# Sheet1.net
KiCad netlist of a schematic drawn in Altium Designer
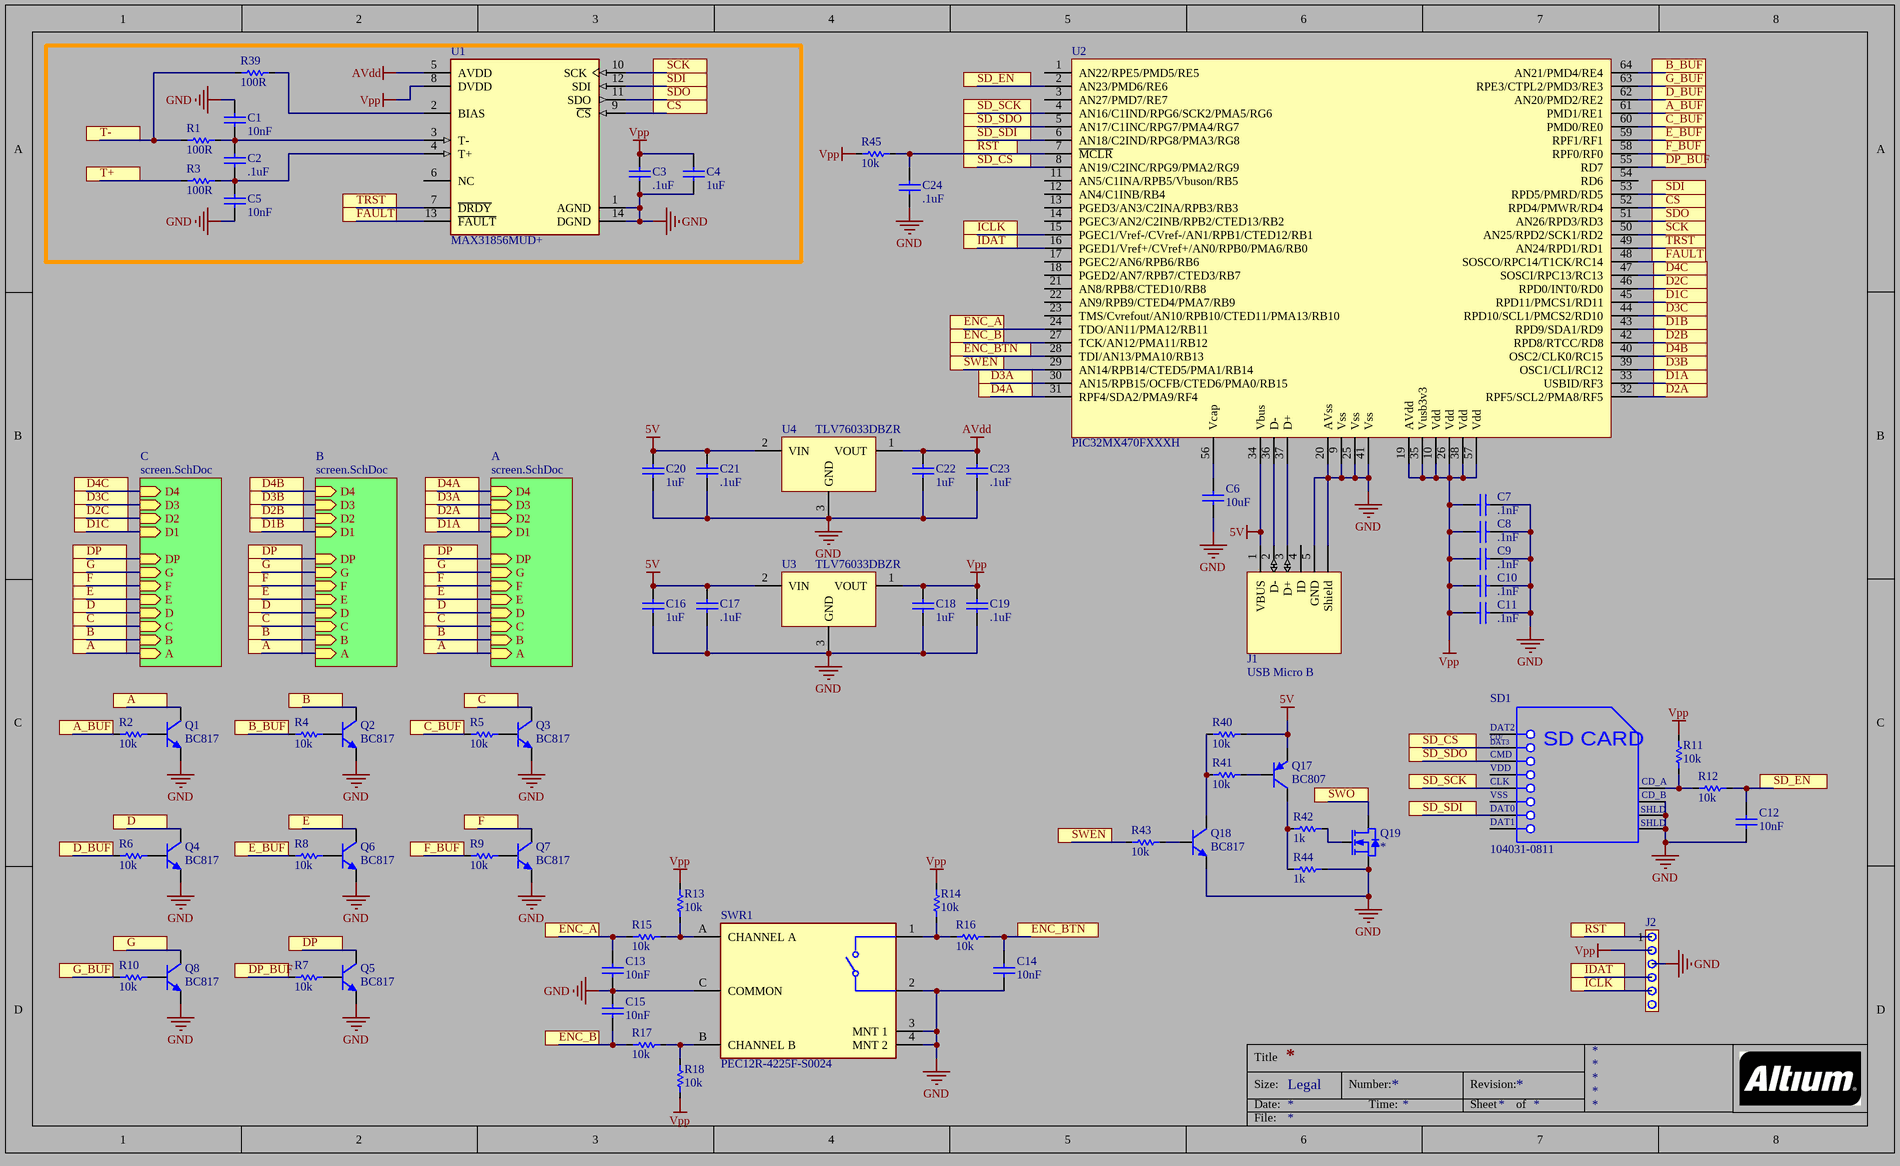
[diagram p0: Sheet1.SchDoc]

(export (version "E")
  (design (tool "Eeschema 10.0.6"))
  (components
    (comp (ref "C1")
      (value "10nF")
      (footprint "Size_0603_N")
      (description "=Value")
      (fields (field (name "Comment") "10nF, *, *, *, Size_0603_N"))
      (libsource (lib "A_Passive") (part "-Cap Non-Pol"))
    )
    (comp (ref "C2")
      (value ".1uF")
      (footprint "Size_0603_N")
      (description "=Value")
      (fields (field (name "Comment") ".1uF, *, *, *, Size_0603_N"))
      (libsource (lib "A_Passive") (part "-Cap Non-Pol"))
    )
    (comp (ref "C3")
      (value ".1uF")
      (footprint "Size_0603_N")
      (description "=Value")
      (fields (field (name "Comment") ".1uF, *, *, *, Size_0603_N"))
      (libsource (lib "A_Passive") (part "-Cap Non-Pol"))
    )
    (comp (ref "C4")
      (value "1uF")
      (footprint "Size_0805_N")
      (description "=Value")
      (fields (field (name "Comment") "1uF, *, *, *, Size_0805_N"))
      (libsource (lib "A_Passive") (part "-Cap Non-Pol"))
    )
    (comp (ref "C5")
      (value "10nF")
      (footprint "Size_0603_N")
      (description "=Value")
      (fields (field (name "Comment") "10nF, *, *, *, Size_0603_N"))
      (libsource (lib "A_Passive") (part "-Cap Non-Pol"))
    )
    (comp (ref "C6")
      (value "10uF")
      (footprint "Size_0805_N")
      (description "=Value")
      (fields (field (name "Comment") "10uF, *, *, *, Size_0805_N"))
      (libsource (lib "A_Passive") (part "-Cap Non-Pol"))
    )
    (comp (ref "C7")
      (value ".1nF")
      (footprint "Size_0603_N")
      (description "=Value")
      (fields (field (name "Comment") ".1nF, *, *, *, Size_0603_N"))
      (libsource (lib "A_Passive") (part "-Cap Non-Pol"))
    )
    (comp (ref "C8")
      (value ".1nF")
      (footprint "Size_0603_N")
      (description "=Value")
      (fields (field (name "Comment") ".1nF, *, *, *, Size_0603_N"))
      (libsource (lib "A_Passive") (part "-Cap Non-Pol"))
    )
    (comp (ref "C9")
      (value ".1nF")
      (footprint "Size_0603_N")
      (description "=Value")
      (fields (field (name "Comment") ".1nF, *, *, *, Size_0603_N"))
      (libsource (lib "A_Passive") (part "-Cap Non-Pol"))
    )
    (comp (ref "C10")
      (value ".1nF")
      (footprint "Size_0603_N")
      (description "=Value")
      (fields (field (name "Comment") ".1nF, *, *, *, Size_0603_N"))
      (libsource (lib "A_Passive") (part "-Cap Non-Pol"))
    )
    (comp (ref "C11")
      (value ".1nF")
      (footprint "Size_0603_N")
      (description "=Value")
      (fields (field (name "Comment") ".1nF, *, *, *, Size_0603_N"))
      (libsource (lib "A_Passive") (part "-Cap Non-Pol"))
    )
    (comp (ref "C12")
      (value "10nF")
      (footprint "Size_0603_N")
      (description "=Value")
      (fields (field (name "Comment") "10nF, *, *, *, Size_0603_N"))
      (libsource (lib "A_Passive") (part "-Cap Non-Pol"))
    )
    (comp (ref "C13")
      (value "10nF")
      (footprint "Size_0603_N")
      (description "=Value")
      (fields (field (name "Comment") "10nF, *, *, *, Size_0603_N"))
      (libsource (lib "A_Passive") (part "-Cap Non-Pol"))
    )
    (comp (ref "C14")
      (value "10nF")
      (footprint "Size_0603_N")
      (description "=Value")
      (fields (field (name "Comment") "10nF, *, *, *, Size_0603_N"))
      (libsource (lib "A_Passive") (part "-Cap Non-Pol"))
    )
    (comp (ref "C15")
      (value "10nF")
      (footprint "Size_0603_N")
      (description "=Value")
      (fields (field (name "Comment") "10nF, *, *, *, Size_0603_N"))
      (libsource (lib "A_Passive") (part "-Cap Non-Pol"))
    )
    (comp (ref "C16")
      (value "1uF")
      (footprint "Size_0805_N")
      (description "=Value")
      (fields (field (name "Comment") "1uF, *, *, *, Size_0805_N"))
      (libsource (lib "A_Passive") (part "-Cap Non-Pol"))
    )
    (comp (ref "C17")
      (value ".1uF")
      (footprint "Size_0603_N")
      (description "=Value")
      (fields (field (name "Comment") ".1uF, *, *, *, Size_0603_N"))
      (libsource (lib "A_Passive") (part "-Cap Non-Pol"))
    )
    (comp (ref "C18")
      (value "1uF")
      (footprint "Size_0805_N")
      (description "=Value")
      (fields (field (name "Comment") "1uF, *, *, *, Size_0805_N"))
      (libsource (lib "A_Passive") (part "-Cap Non-Pol"))
    )
    (comp (ref "C19")
      (value ".1uF")
      (footprint "Size_0603_N")
      (description "=Value")
      (fields (field (name "Comment") ".1uF, *, *, *, Size_0603_N"))
      (libsource (lib "A_Passive") (part "-Cap Non-Pol"))
    )
    (comp (ref "C20")
      (value "1uF")
      (footprint "Size_0805_N")
      (description "=Value")
      (fields (field (name "Comment") "1uF, *, *, *, Size_0805_N"))
      (libsource (lib "A_Passive") (part "-Cap Non-Pol"))
    )
    (comp (ref "C21")
      (value ".1uF")
      (footprint "Size_0603_N")
      (description "=Value")
      (fields (field (name "Comment") ".1uF, *, *, *, Size_0603_N"))
      (libsource (lib "A_Passive") (part "-Cap Non-Pol"))
    )
    (comp (ref "C22")
      (value "1uF")
      (footprint "Size_0805_N")
      (description "=Value")
      (fields (field (name "Comment") "1uF, *, *, *, Size_0805_N"))
      (libsource (lib "A_Passive") (part "-Cap Non-Pol"))
    )
    (comp (ref "C23")
      (value ".1uF")
      (footprint "Size_0603_N")
      (description "=Value")
      (fields (field (name "Comment") ".1uF, *, *, *, Size_0603_N"))
      (libsource (lib "A_Passive") (part "-Cap Non-Pol"))
    )
    (comp (ref "C24")
      (value ".1uF")
      (footprint "Size_0603_N")
      (description "=Value")
      (fields (field (name "Comment") ".1uF, *, *, *, Size_0603_N"))
      (libsource (lib "A_Passive") (part "-Cap Non-Pol"))
    )
    (comp (ref "J1")
      (value "USB Micro B")
      (footprint "USB-MICRO-B (10118194-0001LF)")
      (description "Female Micro USB Type B")
      (libsource (lib "A_Connector") (part "USB Micro B"))
    )
    (comp (ref "J2")
      (value "~")
      (footprint "HDR1X6 VERT - L")
      (libsource (lib "A_Connector") (part "Header 1-6"))
    )
    (comp (ref "Q1")
      (value "BC817")
      (footprint "SOT23-3")
      (description "NPN General Purpose")
      (libsource (lib "A_Semi") (part "1-BJT_NPN"))
    )
    (comp (ref "Q2")
      (value "BC817")
      (footprint "SOT23-3")
      (description "NPN General Purpose")
      (libsource (lib "A_Semi") (part "1-BJT_NPN"))
    )
    (comp (ref "Q3")
      (value "BC817")
      (footprint "SOT23-3")
      (description "NPN General Purpose")
      (libsource (lib "A_Semi") (part "1-BJT_NPN"))
    )
    (comp (ref "Q4")
      (value "BC817")
      (footprint "SOT23-3")
      (description "NPN General Purpose")
      (libsource (lib "A_Semi") (part "1-BJT_NPN"))
    )
    (comp (ref "Q5")
      (value "BC817")
      (footprint "SOT23-3")
      (description "NPN General Purpose")
      (libsource (lib "A_Semi") (part "1-BJT_NPN"))
    )
    (comp (ref "Q6")
      (value "BC817")
      (footprint "SOT23-3")
      (description "NPN General Purpose")
      (libsource (lib "A_Semi") (part "1-BJT_NPN"))
    )
    (comp (ref "Q7")
      (value "BC817")
      (footprint "SOT23-3")
      (description "NPN General Purpose")
      (libsource (lib "A_Semi") (part "1-BJT_NPN"))
    )
    (comp (ref "Q8")
      (value "BC817")
      (footprint "SOT23-3")
      (description "NPN General Purpose")
      (libsource (lib "A_Semi") (part "1-BJT_NPN"))
    )
    (comp (ref "Q17") (value "BC807") (footprint "SOT23-3") (libsource (lib "A_Semi") (part "1-BJT-PNP")))
    (comp (ref "Q18")
      (value "BC817")
      (footprint "SOT23-3")
      (description "NPN General Purpose")
      (libsource (lib "A_Semi") (part "1-BJT_NPN"))
    )
    (comp (ref "Q19")
      (value "*")
      (footprint "SOT23-3")
      (description "N-Channel Mosfet")
      (libsource (lib "A_Semi") (part "1-Mosfet_N"))
    )
    (comp (ref "R1")
      (value "100R")
      (footprint "Size_0603_N")
      (description "=Value")
      (fields (field (name "TOLERANCE") "1%") (field (name "Comment") "100R, *"))
      (libsource (lib "A_Passive") (part "-Res"))
    )
    (comp (ref "R2")
      (value "10k")
      (footprint "Size_0603_N")
      (description "=Value")
      (fields (field (name "TOLERANCE") ".1%") (field (name "Comment") "10k, *"))
      (libsource (lib "A_Passive") (part "-Res"))
    )
    (comp (ref "R3")
      (value "100R")
      (footprint "Size_0603_N")
      (description "=Value")
      (fields (field (name "TOLERANCE") "1%") (field (name "Comment") "100R, *"))
      (libsource (lib "A_Passive") (part "-Res"))
    )
    (comp (ref "R4")
      (value "10k")
      (footprint "Size_0603_N")
      (description "=Value")
      (fields (field (name "TOLERANCE") ".1%") (field (name "Comment") "10k, *"))
      (libsource (lib "A_Passive") (part "-Res"))
    )
    (comp (ref "R5")
      (value "10k")
      (footprint "Size_0603_N")
      (description "=Value")
      (fields (field (name "TOLERANCE") ".1%") (field (name "Comment") "10k, *"))
      (libsource (lib "A_Passive") (part "-Res"))
    )
    (comp (ref "R6")
      (value "10k")
      (footprint "Size_0603_N")
      (description "=Value")
      (fields (field (name "TOLERANCE") ".1%") (field (name "Comment") "10k, *"))
      (libsource (lib "A_Passive") (part "-Res"))
    )
    (comp (ref "R7")
      (value "10k")
      (footprint "Size_0603_N")
      (description "=Value")
      (fields (field (name "TOLERANCE") ".1%") (field (name "Comment") "10k, *"))
      (libsource (lib "A_Passive") (part "-Res"))
    )
    (comp (ref "R8")
      (value "10k")
      (footprint "Size_0603_N")
      (description "=Value")
      (fields (field (name "TOLERANCE") ".1%") (field (name "Comment") "10k, *"))
      (libsource (lib "A_Passive") (part "-Res"))
    )
    (comp (ref "R9")
      (value "10k")
      (footprint "Size_0603_N")
      (description "=Value")
      (fields (field (name "TOLERANCE") ".1%") (field (name "Comment") "10k, *"))
      (libsource (lib "A_Passive") (part "-Res"))
    )
    (comp (ref "R10")
      (value "10k")
      (footprint "Size_0603_N")
      (description "=Value")
      (fields (field (name "TOLERANCE") ".1%") (field (name "Comment") "10k, *"))
      (libsource (lib "A_Passive") (part "-Res"))
    )
    (comp (ref "R11")
      (value "10k")
      (footprint "Size_0603_N")
      (description "=Value")
      (fields (field (name "TOLERANCE") ".1%") (field (name "Comment") "10k, *"))
      (libsource (lib "A_Passive") (part "-Res"))
    )
    (comp (ref "R12")
      (value "10k")
      (footprint "Size_0603_N")
      (description "=Value")
      (fields (field (name "TOLERANCE") ".1%") (field (name "Comment") "10k, *"))
      (libsource (lib "A_Passive") (part "-Res"))
    )
    (comp (ref "R13")
      (value "10k")
      (footprint "Size_0603_N")
      (description "=Value")
      (fields (field (name "TOLERANCE") ".1%") (field (name "Comment") "10k, *"))
      (libsource (lib "A_Passive") (part "-Res"))
    )
    (comp (ref "R14")
      (value "10k")
      (footprint "Size_0603_N")
      (description "=Value")
      (fields (field (name "TOLERANCE") ".1%") (field (name "Comment") "10k, *"))
      (libsource (lib "A_Passive") (part "-Res"))
    )
    (comp (ref "R15")
      (value "10k")
      (footprint "Size_0603_N")
      (description "=Value")
      (fields (field (name "TOLERANCE") ".1%") (field (name "Comment") "10k, *"))
      (libsource (lib "A_Passive") (part "-Res"))
    )
    (comp (ref "R16")
      (value "10k")
      (footprint "Size_0603_N")
      (description "=Value")
      (fields (field (name "TOLERANCE") ".1%") (field (name "Comment") "10k, *"))
      (libsource (lib "A_Passive") (part "-Res"))
    )
    (comp (ref "R17")
      (value "10k")
      (footprint "Size_0603_N")
      (description "=Value")
      (fields (field (name "TOLERANCE") ".1%") (field (name "Comment") "10k, *"))
      (libsource (lib "A_Passive") (part "-Res"))
    )
    (comp (ref "R18")
      (value "10k")
      (footprint "Size_0603_N")
      (description "=Value")
      (fields (field (name "TOLERANCE") ".1%") (field (name "Comment") "10k, *"))
      (libsource (lib "A_Passive") (part "-Res"))
    )
    (comp (ref "R39")
      (value "100R")
      (footprint "Size_0603_N")
      (description "=Value")
      (fields (field (name "TOLERANCE") "1%") (field (name "Comment") "100R, *"))
      (libsource (lib "A_Passive") (part "-Res"))
    )
    (comp (ref "R40")
      (value "10k")
      (footprint "Size_0603_N")
      (description "=Value")
      (fields (field (name "TOLERANCE") ".1%") (field (name "Comment") "10k, *"))
      (libsource (lib "A_Passive") (part "-Res"))
    )
    (comp (ref "R41")
      (value "10k")
      (footprint "Size_0603_N")
      (description "=Value")
      (fields (field (name "TOLERANCE") ".1%") (field (name "Comment") "10k, *"))
      (libsource (lib "A_Passive") (part "-Res"))
    )
    (comp (ref "R42")
      (value "1k")
      (footprint "Size_0603_N")
      (description "=Value")
      (fields (field (name "TOLERANCE") ".1%") (field (name "Comment") "1k, *"))
      (libsource (lib "A_Passive") (part "-Res"))
    )
    (comp (ref "R43")
      (value "10k")
      (footprint "Size_0603_N")
      (description "=Value")
      (fields (field (name "TOLERANCE") ".1%") (field (name "Comment") "10k, *"))
      (libsource (lib "A_Passive") (part "-Res"))
    )
    (comp (ref "R44")
      (value "1k")
      (footprint "Size_0603_N")
      (description "=Value")
      (fields (field (name "TOLERANCE") ".1%") (field (name "Comment") "1k, *"))
      (libsource (lib "A_Passive") (part "-Res"))
    )
    (comp (ref "R45")
      (value "10k")
      (footprint "Size_0603_N")
      (description "=Value")
      (fields (field (name "TOLERANCE") ".1%") (field (name "Comment") "10k, *"))
      (libsource (lib "A_Passive") (part "-Res"))
    )
    (comp (ref "SD1")
      (value "104031-0811")
      (footprint "MOLX-104031-0811_V")
      (description "Micro SD Card, RA, -25 to 85 degC, 8-Pin SMD, RoHS, Tape and Reel")
      (fields (field (name "MANUFACTURER") "Molex"))
      (libsource (lib "Altium Content Vault") (part "CN-SD-8-2SW-2S"))
    )
    (comp (ref "SWR1")
      (value "PEC12R-4225F-S0024")
      (footprint "PEC12R")
      (libsource (lib "A_Active") (part "PEC12R-4225F-S0024"))
    )
    (comp (ref "U1")
      (value "MAX31856MUD+")
      (footprint "FP-U14-2-MFG")
      (description "IC CONV THERMOCOUPLE 14TSSOP")
      (libsource (lib "Altium Content Vault") (part "746ee3d58a922cadd982a8de1b076a0"))
    )
    (comp (ref "U2")
      (value "PIC32MX470FXXXH")
      (footprint "TSQFP50P1200X1200X120-64M")
      (libsource (lib "A_Semi") (part "MCU_PIC32MX470FXXXH"))
    )
    (comp (ref "U3")
      (value "TLV76033DBZR")
      (footprint "SOT23-3")
      (libsource (lib "A_Semi") (part "1-linreg_3 O1I2G3"))
    )
    (comp (ref "U4")
      (value "TLV76033DBZR")
      (footprint "SOT23-3")
      (libsource (lib "A_Semi") (part "1-linreg_3 O1I2G3"))
    )
  )
  (nets
    (net (code "1") (name "/A") (class "Default")
      (node (ref "Q1") (pin "3") (pinfunction "C_3") (pintype "passive"))
    )
    (net (code "2") (name "/A_BUF") (class "Default")
      (node (ref "R2") (pin "2") (pinfunction "2_2") (pintype "passive"))
      (node (ref "U2") (pin "61") (pinfunction "PMD1/RE1_61") (pintype "passive"))
    )
    (net (code "3") (name "/B") (class "Default")
      (node (ref "Q2") (pin "3") (pinfunction "C_3") (pintype "passive"))
    )
    (net (code "4") (name "/B_BUF") (class "Default")
      (node (ref "R4") (pin "2") (pinfunction "2_2") (pintype "passive"))
      (node (ref "U2") (pin "64") (pinfunction "AN21/PMD4/RE4_64") (pintype "passive"))
    )
    (net (code "5") (name "/C") (class "Default")
      (node (ref "Q3") (pin "3") (pinfunction "C_3") (pintype "passive"))
    )
    (net (code "6") (name "/CS") (class "Default")
      (node (ref "U1") (pin "9") (pinfunction "~{CS}_9") (pintype "input"))
      (node (ref "U2") (pin "52") (pinfunction "RPD4/PMWR/RD4_52") (pintype "passive"))
    )
    (net (code "7") (name "/C_BUF") (class "Default")
      (node (ref "R5") (pin "2") (pinfunction "2_2") (pintype "passive"))
      (node (ref "U2") (pin "60") (pinfunction "PMD0/RE0_60") (pintype "passive"))
    )
    (net (code "8") (name "/D") (class "Default")
      (node (ref "Q4") (pin "3") (pinfunction "C_3") (pintype "passive"))
    )
    (net (code "9") (name "/D1A") (class "Default")
      (node (ref "U2") (pin "33") (pinfunction "USBID/RF3_33") (pintype "passive"))
    )
    (net (code "10") (name "/D1B") (class "Default")
      (node (ref "U2") (pin "43") (pinfunction "RPD9/SDA1/RD9_43") (pintype "passive"))
    )
    (net (code "11") (name "/D1C") (class "Default")
      (node (ref "U2") (pin "45") (pinfunction "RPD11/PMCS1/RD11_45") (pintype "passive"))
    )
    (net (code "12") (name "/D2A") (class "Default")
      (node (ref "U2") (pin "32") (pinfunction "RPF5/SCL2/PMA8/RF5_32") (pintype "passive"))
    )
    (net (code "13") (name "/D2B") (class "Default")
      (node (ref "U2") (pin "42") (pinfunction "RPD8/RTCC/RD8_42") (pintype "passive"))
    )
    (net (code "14") (name "/D2C") (class "Default")
      (node (ref "U2") (pin "46") (pinfunction "RPD0/INT0/RD0_46") (pintype "passive"))
    )
    (net (code "15") (name "/D3A") (class "Default")
      (node (ref "U2") (pin "30") (pinfunction "AN15/RPB15/OCFB/CTED6/PMA0/RB15_30") (pintype "passive"))
    )
    (net (code "16") (name "/D3B") (class "Default")
      (node (ref "U2") (pin "39") (pinfunction "OSC1/CLI/RC12_39") (pintype "passive"))
    )
    (net (code "17") (name "/D3C") (class "Default")
      (node (ref "U2") (pin "44") (pinfunction "RPD10/SCL1/PMCS2/RD10_44") (pintype "passive"))
    )
    (net (code "18") (name "/D4A") (class "Default")
      (node (ref "U2") (pin "31") (pinfunction "RPF4/SDA2/PMA9/RF4_31") (pintype "passive"))
    )
    (net (code "19") (name "/D4B") (class "Default")
      (node (ref "U2") (pin "40") (pinfunction "OSC2/CLK0/RC15_40") (pintype "passive"))
    )
    (net (code "20") (name "/D4C") (class "Default")
      (node (ref "U2") (pin "47") (pinfunction "SOSCI/RPC13/RC13_47") (pintype "passive"))
    )
    (net (code "21") (name "/DP") (class "Default")
      (node (ref "Q5") (pin "3") (pinfunction "C_3") (pintype "passive"))
    )
    (net (code "22") (name "/DP_BUF") (class "Default")
      (node (ref "R7") (pin "2") (pinfunction "2_2") (pintype "passive"))
      (node (ref "U2") (pin "55") (pinfunction "RD7_55") (pintype "passive"))
    )
    (net (code "23") (name "/D_BUF") (class "Default")
      (node (ref "R6") (pin "2") (pinfunction "2_2") (pintype "passive"))
      (node (ref "U2") (pin "62") (pinfunction "AN20/PMD2/RE2_62") (pintype "passive"))
    )
    (net (code "24") (name "/E") (class "Default")
      (node (ref "Q6") (pin "3") (pinfunction "C_3") (pintype "passive"))
    )
    (net (code "25") (name "/ENC_A") (class "Default")
      (node (ref "C13") (pin "2") (pinfunction "2_2") (pintype "passive"))
      (node (ref "R15") (pin "1") (pinfunction "1_1") (pintype "passive"))
      (node (ref "U2") (pin "24") (pinfunction "TDO/AN11/PMA12/RB11_24") (pintype "passive"))
    )
    (net (code "26") (name "/ENC_B") (class "Default")
      (node (ref "C15") (pin "1") (pinfunction "1_1") (pintype "passive"))
      (node (ref "R17") (pin "1") (pinfunction "1_1") (pintype "passive"))
      (node (ref "U2") (pin "27") (pinfunction "TCK/AN12/PMA11/RB12_27") (pintype "passive"))
    )
    (net (code "27") (name "/ENC_BTN") (class "Default")
      (node (ref "C14") (pin "2") (pinfunction "2_2") (pintype "passive"))
      (node (ref "R16") (pin "2") (pinfunction "2_2") (pintype "passive"))
      (node (ref "U2") (pin "28") (pinfunction "TDI/AN13/PMA10/RB13_28") (pintype "passive"))
    )
    (net (code "28") (name "/E_BUF") (class "Default")
      (node (ref "R8") (pin "2") (pinfunction "2_2") (pintype "passive"))
      (node (ref "U2") (pin "59") (pinfunction "RPF1/RF1_59") (pintype "passive"))
    )
    (net (code "29") (name "/F") (class "Default")
      (node (ref "Q7") (pin "3") (pinfunction "C_3") (pintype "passive"))
    )
    (net (code "30") (name "/FAULT") (class "Default")
      (node (ref "U1") (pin "13") (pinfunction "~{FAULT}_13") (pintype "passive"))
      (node (ref "U2") (pin "48") (pinfunction "SOSCO/RPC14/T1CK/RC14_48") (pintype "passive"))
    )
    (net (code "31") (name "/F_BUF") (class "Default")
      (node (ref "R9") (pin "2") (pinfunction "2_2") (pintype "passive"))
      (node (ref "U2") (pin "58") (pinfunction "RPF0/RF0_58") (pintype "passive"))
    )
    (net (code "32") (name "/G") (class "Default")
      (node (ref "Q8") (pin "3") (pinfunction "C_3") (pintype "passive"))
    )
    (net (code "33") (name "/G_BUF") (class "Default")
      (node (ref "R10") (pin "2") (pinfunction "2_2") (pintype "passive"))
      (node (ref "U2") (pin "63") (pinfunction "RPE3/CTPL2/PMD3/RE3_63") (pintype "passive"))
    )
    (net (code "34") (name "/ICLK") (class "Default")
      (node (ref "J2") (pin "5") (pinfunction "5_5") (pintype "passive"))
      (node (ref "U2") (pin "15") (pinfunction "PGEC1/Vref-/CVref-/AN1/RPB1/CTED12/RB1_15") (pintype "passive"))
    )
    (net (code "35") (name "/IDAT") (class "Default")
      (node (ref "J2") (pin "4") (pinfunction "4_4") (pintype "passive"))
      (node (ref "U2") (pin "16") (pinfunction "PGED1/Vref+/CVref+/AN0/RPB0/PMA6/RB0_16") (pintype "passive"))
    )
    (net (code "36") (name "/RST") (class "Default")
      (node (ref "C24") (pin "2") (pinfunction "2_2") (pintype "passive"))
      (node (ref "J2") (pin "1") (pinfunction "1_1") (pintype "passive"))
      (node (ref "R45") (pin "2") (pinfunction "2_2") (pintype "passive"))
      (node (ref "U2") (pin "7") (pinfunction "~{MCLR}_7") (pintype "passive"))
    )
    (net (code "37") (name "/SCK") (class "Default")
      (node (ref "U1") (pin "10") (pinfunction "SCK_10") (pintype "input"))
      (node (ref "U2") (pin "50") (pinfunction "AN25/RPD2/SCK1/RD2_50") (pintype "passive"))
    )
    (net (code "38") (name "/SDI") (class "Default")
      (node (ref "U1") (pin "12") (pinfunction "SDI_12") (pintype "input"))
      (node (ref "U2") (pin "53") (pinfunction "RPD5/PMRD/RD5_53") (pintype "passive"))
    )
    (net (code "39") (name "/SDO") (class "Default")
      (node (ref "U1") (pin "11") (pinfunction "SDO_11") (pintype "output"))
      (node (ref "U2") (pin "51") (pinfunction "AN26/RPD3/RD3_51") (pintype "passive"))
    )
    (net (code "40") (name "/SD_CS") (class "Default")
      (node (ref "SD1") (pin "2") (pinfunction "CMD_2") (pintype "passive"))
      (node (ref "U2") (pin "8") (pinfunction "AN19/C2INC/RPG9/PMA2/RG9_8") (pintype "passive"))
    )
    (net (code "41") (name "/SD_EN") (class "Default")
      (node (ref "C12") (pin "2") (pinfunction "2_2") (pintype "passive"))
      (node (ref "R12") (pin "2") (pinfunction "2_2") (pintype "passive"))
      (node (ref "U2") (pin "2") (pinfunction "AN23/PMD6/RE6_2") (pintype "passive"))
    )
    (net (code "42") (name "/SD_SCK") (class "Default")
      (node (ref "SD1") (pin "5") (pinfunction "CLK_5") (pintype "passive"))
      (node (ref "U2") (pin "4") (pinfunction "AN16/C1IND/RPG6/SCK2/PMA5/RG6_4") (pintype "passive"))
    )
    (net (code "43") (name "/SD_SDI") (class "Default")
      (node (ref "SD1") (pin "7") (pinfunction "DAT0_7") (pintype "passive"))
      (node (ref "U2") (pin "6") (pinfunction "AN18/C2IND/RPG8/PMA3/RG8_6") (pintype "passive"))
    )
    (net (code "44") (name "/SD_SDO") (class "Default")
      (node (ref "SD1") (pin "3") (pinfunction "VSS1_3") (pintype "passive"))
      (node (ref "U2") (pin "5") (pinfunction "AN17/C1INC/RPG7/PMA4/RG7_5") (pintype "passive"))
    )
    (net (code "45") (name "/SWEN") (class "Default")
      (node (ref "R43") (pin "1") (pinfunction "1_1") (pintype "passive"))
      (node (ref "U2") (pin "29") (pinfunction "AN14/RPB14/CTED5/PMA1/RB14_29") (pintype "passive"))
    )
    (net (code "46") (name "/SWO") (class "Default")
      (node (ref "Q19") (pin "3") (pinfunction "D_3") (pintype "passive"))
    )
    (net (code "47") (name "/T+") (class "Default")
      (node (ref "R3") (pin "1") (pinfunction "1_1") (pintype "passive"))
    )
    (net (code "48") (name "/T-") (class "Default")
      (node (ref "R1") (pin "1") (pinfunction "1_1") (pintype "passive"))
      (node (ref "R39") (pin "1") (pinfunction "1_1") (pintype "passive"))
    )
    (net (code "49") (name "/TRST") (class "Default")
      (node (ref "U1") (pin "7") (pinfunction "~{DRDY}_7") (pintype "passive"))
      (node (ref "U2") (pin "49") (pinfunction "AN24/RPD1/RD1_49") (pintype "passive"))
    )
    (net (code "50") (name "5V") (class "Default")
      (node (ref "C16") (pin "2") (pinfunction "2_2") (pintype "passive"))
      (node (ref "C17") (pin "2") (pinfunction "2_2") (pintype "passive"))
      (node (ref "C20") (pin "2") (pinfunction "2_2") (pintype "passive"))
      (node (ref "C21") (pin "2") (pinfunction "2_2") (pintype "passive"))
      (node (ref "J1") (pin "1") (pinfunction "VBUS_1") (pintype "power_in"))
      (node (ref "Q17") (pin "2") (pinfunction "E_2") (pintype "passive"))
      (node (ref "R40") (pin "2") (pinfunction "2_2") (pintype "passive"))
      (node (ref "U2") (pin "34") (pinfunction "Vbus_34") (pintype "passive"))
      (node (ref "U3") (pin "2") (pinfunction "VIN_2") (pintype "power_in"))
      (node (ref "U4") (pin "2") (pinfunction "VIN_2") (pintype "power_in"))
    )
    (net (code "51") (name "AVdd") (class "Default")
      (node (ref "C22") (pin "2") (pinfunction "2_2") (pintype "passive"))
      (node (ref "C23") (pin "2") (pinfunction "2_2") (pintype "passive"))
      (node (ref "U1") (pin "5") (pinfunction "AVDD_5") (pintype "power_in"))
      (node (ref "U4") (pin "1") (pinfunction "VOUT_1") (pintype "power_in"))
    )
    (net (code "52") (name "GND") (class "Default")
      (node (ref "C1") (pin "2") (pinfunction "2_2") (pintype "passive"))
      (node (ref "C10") (pin "2") (pinfunction "2_2") (pintype "passive"))
      (node (ref "C11") (pin "2") (pinfunction "2_2") (pintype "passive"))
      (node (ref "C12") (pin "1") (pinfunction "1_1") (pintype "passive"))
      (node (ref "C13") (pin "1") (pinfunction "1_1") (pintype "passive"))
      (node (ref "C14") (pin "1") (pinfunction "1_1") (pintype "passive"))
      (node (ref "C15") (pin "2") (pinfunction "2_2") (pintype "passive"))
      (node (ref "C16") (pin "1") (pinfunction "1_1") (pintype "passive"))
      (node (ref "C17") (pin "1") (pinfunction "1_1") (pintype "passive"))
      (node (ref "C18") (pin "1") (pinfunction "1_1") (pintype "passive"))
      (node (ref "C19") (pin "1") (pinfunction "1_1") (pintype "passive"))
      (node (ref "C20") (pin "1") (pinfunction "1_1") (pintype "passive"))
      (node (ref "C21") (pin "1") (pinfunction "1_1") (pintype "passive"))
      (node (ref "C22") (pin "1") (pinfunction "1_1") (pintype "passive"))
      (node (ref "C23") (pin "1") (pinfunction "1_1") (pintype "passive"))
      (node (ref "C24") (pin "1") (pinfunction "1_1") (pintype "passive"))
      (node (ref "C3") (pin "1") (pinfunction "1_1") (pintype "passive"))
      (node (ref "C4") (pin "1") (pinfunction "1_1") (pintype "passive"))
      (node (ref "C5") (pin "1") (pinfunction "1_1") (pintype "passive"))
      (node (ref "C6") (pin "1") (pinfunction "1_1") (pintype "passive"))
      (node (ref "C7") (pin "2") (pinfunction "2_2") (pintype "passive"))
      (node (ref "C8") (pin "2") (pinfunction "2_2") (pintype "passive"))
      (node (ref "C9") (pin "2") (pinfunction "2_2") (pintype "passive"))
      (node (ref "J1") (pin "5") (pinfunction "GND_5") (pintype "power_in"))
      (node (ref "J1") (pin "Shield") (pinfunction "Shield_Shield") (pintype "passive"))
      (node (ref "J2") (pin "3") (pinfunction "3_3") (pintype "passive"))
      (node (ref "Q1") (pin "2") (pinfunction "E_2") (pintype "passive"))
      (node (ref "Q18") (pin "2") (pinfunction "E_2") (pintype "passive"))
      (node (ref "Q19") (pin "2") (pinfunction "S_2") (pintype "passive"))
      (node (ref "Q2") (pin "2") (pinfunction "E_2") (pintype "passive"))
      (node (ref "Q3") (pin "2") (pinfunction "E_2") (pintype "passive"))
      (node (ref "Q4") (pin "2") (pinfunction "E_2") (pintype "passive"))
      (node (ref "Q5") (pin "2") (pinfunction "E_2") (pintype "passive"))
      (node (ref "Q6") (pin "2") (pinfunction "E_2") (pintype "passive"))
      (node (ref "Q7") (pin "2") (pinfunction "E_2") (pintype "passive"))
      (node (ref "Q8") (pin "2") (pinfunction "E_2") (pintype "passive"))
      (node (ref "R44") (pin "2") (pinfunction "2_2") (pintype "passive"))
      (node (ref "SD1") (pin "10") (pinfunction "CD_B_10") (pintype "passive"))
      (node (ref "SD1") (pin "11") (pinfunction "SHLD1_11") (pintype "passive"))
      (node (ref "SD1") (pin "12") (pinfunction "SHLD2_12") (pintype "passive"))
      (node (ref "SWR1") (pin "2") (pinfunction "2_2") (pintype "passive"))
      (node (ref "SWR1") (pin "3") (pinfunction "MNT_1_3") (pintype "passive"))
      (node (ref "SWR1") (pin "4") (pinfunction "MNT_2_4") (pintype "passive"))
      (node (ref "SWR1") (pin "C") (pinfunction "COMMON_C") (pintype "passive"))
      (node (ref "U1") (pin "1") (pinfunction "AGND_1") (pintype "power_in"))
      (node (ref "U1") (pin "14") (pinfunction "DGND_14") (pintype "power_in"))
      (node (ref "U2") (pin "20") (pinfunction "AVss_20") (pintype "passive"))
      (node (ref "U2") (pin "25") (pinfunction "Vss_25") (pintype "passive"))
      (node (ref "U2") (pin "41") (pinfunction "Vss_41") (pintype "passive"))
      (node (ref "U2") (pin "9") (pinfunction "Vss_9") (pintype "passive"))
      (node (ref "U3") (pin "3") (pinfunction "GND_3") (pintype "power_in"))
      (node (ref "U4") (pin "3") (pinfunction "GND_3") (pintype "power_in"))
    )
    (net (code "53") (name "Net-(J1-D+)") (class "Default")
      (node (ref "J1") (pin "3") (pinfunction "D+_3") (pintype "bidirectional"))
      (node (ref "U2") (pin "37") (pinfunction "D+_37") (pintype "passive"))
    )
    (net (code "54") (name "Net-(J1-D-)") (class "Default")
      (node (ref "J1") (pin "2") (pinfunction "D-_2") (pintype "bidirectional"))
      (node (ref "U2") (pin "36") (pinfunction "D-_36") (pintype "passive"))
    )
    (net (code "55") (name "Net-(Q1-B)") (class "Default")
      (node (ref "Q1") (pin "1") (pinfunction "B_1") (pintype "passive"))
      (node (ref "R2") (pin "1") (pinfunction "1_1") (pintype "passive"))
    )
    (net (code "56") (name "Net-(Q2-B)") (class "Default")
      (node (ref "Q2") (pin "1") (pinfunction "B_1") (pintype "passive"))
      (node (ref "R4") (pin "1") (pinfunction "1_1") (pintype "passive"))
    )
    (net (code "57") (name "Net-(Q3-B)") (class "Default")
      (node (ref "Q3") (pin "1") (pinfunction "B_1") (pintype "passive"))
      (node (ref "R5") (pin "1") (pinfunction "1_1") (pintype "passive"))
    )
    (net (code "58") (name "Net-(Q4-B)") (class "Default")
      (node (ref "Q4") (pin "1") (pinfunction "B_1") (pintype "passive"))
      (node (ref "R6") (pin "1") (pinfunction "1_1") (pintype "passive"))
    )
    (net (code "59") (name "Net-(Q5-B)") (class "Default")
      (node (ref "Q5") (pin "1") (pinfunction "B_1") (pintype "passive"))
      (node (ref "R7") (pin "1") (pinfunction "1_1") (pintype "passive"))
    )
    (net (code "60") (name "Net-(Q6-B)") (class "Default")
      (node (ref "Q6") (pin "1") (pinfunction "B_1") (pintype "passive"))
      (node (ref "R8") (pin "1") (pinfunction "1_1") (pintype "passive"))
    )
    (net (code "61") (name "Net-(Q7-B)") (class "Default")
      (node (ref "Q7") (pin "1") (pinfunction "B_1") (pintype "passive"))
      (node (ref "R9") (pin "1") (pinfunction "1_1") (pintype "passive"))
    )
    (net (code "62") (name "Net-(Q8-B)") (class "Default")
      (node (ref "Q8") (pin "1") (pinfunction "B_1") (pintype "passive"))
      (node (ref "R10") (pin "1") (pinfunction "1_1") (pintype "passive"))
    )
    (net (code "63") (name "Net-(Q17-B)") (class "Default")
      (node (ref "Q17") (pin "1") (pinfunction "B_1") (pintype "passive"))
      (node (ref "R41") (pin "2") (pinfunction "2_2") (pintype "passive"))
    )
    (net (code "64") (name "Net-(Q17-C)") (class "Default")
      (node (ref "Q17") (pin "3") (pinfunction "C_3") (pintype "passive"))
      (node (ref "R42") (pin "1") (pinfunction "1_1") (pintype "passive"))
      (node (ref "R44") (pin "1") (pinfunction "1_1") (pintype "passive"))
    )
    (net (code "65") (name "Net-(Q18-B)") (class "Default")
      (node (ref "Q18") (pin "1") (pinfunction "B_1") (pintype "passive"))
      (node (ref "R43") (pin "2") (pinfunction "2_2") (pintype "passive"))
    )
    (net (code "66") (name "Net-(Q18-C)") (class "Default")
      (node (ref "Q18") (pin "3") (pinfunction "C_3") (pintype "passive"))
      (node (ref "R40") (pin "1") (pinfunction "1_1") (pintype "passive"))
      (node (ref "R41") (pin "1") (pinfunction "1_1") (pintype "passive"))
    )
    (net (code "67") (name "Net-(Q19-G)") (class "Default")
      (node (ref "Q19") (pin "1") (pinfunction "G_1") (pintype "passive"))
      (node (ref "R42") (pin "2") (pinfunction "2_2") (pintype "passive"))
    )
    (net (code "68") (name "Net-(R14-Pad2)") (class "Default")
      (node (ref "R14") (pin "2") (pinfunction "2_2") (pintype "passive"))
      (node (ref "R16") (pin "1") (pinfunction "1_1") (pintype "passive"))
      (node (ref "SWR1") (pin "1") (pinfunction "1_1") (pintype "passive"))
    )
    (net (code "69") (name "Net-(SD1-CD_A)") (class "Default")
      (node (ref "R11") (pin "2") (pinfunction "2_2") (pintype "passive"))
      (node (ref "R12") (pin "1") (pinfunction "1_1") (pintype "passive"))
      (node (ref "SD1") (pin "9") (pinfunction "CD_A_9") (pintype "passive"))
    )
    (net (code "70") (name "Net-(SWR1-CHANNEL_A)") (class "Default")
      (node (ref "R13") (pin "2") (pinfunction "2_2") (pintype "passive"))
      (node (ref "R15") (pin "2") (pinfunction "2_2") (pintype "passive"))
      (node (ref "SWR1") (pin "A") (pinfunction "CHANNEL_A_A") (pintype "passive"))
    )
    (net (code "71") (name "Net-(SWR1-CHANNEL_B)") (class "Default")
      (node (ref "R17") (pin "2") (pinfunction "2_2") (pintype "passive"))
      (node (ref "R18") (pin "1") (pinfunction "1_1") (pintype "passive"))
      (node (ref "SWR1") (pin "B") (pinfunction "CHANNEL_B_B") (pintype "passive"))
    )
    (net (code "72") (name "Net-(U1-BIAS)") (class "Default")
      (node (ref "R39") (pin "2") (pinfunction "2_2") (pintype "passive"))
      (node (ref "U1") (pin "2") (pinfunction "BIAS_2") (pintype "passive"))
    )
    (net (code "73") (name "Net-(U1-T+)") (class "Default")
      (node (ref "C2") (pin "1") (pinfunction "1_1") (pintype "passive"))
      (node (ref "C5") (pin "2") (pinfunction "2_2") (pintype "passive"))
      (node (ref "R3") (pin "2") (pinfunction "2_2") (pintype "passive"))
      (node (ref "U1") (pin "4") (pinfunction "T+_4") (pintype "input"))
    )
    (net (code "74") (name "Net-(U1-T-)") (class "Default")
      (node (ref "C1") (pin "1") (pinfunction "1_1") (pintype "passive"))
      (node (ref "C2") (pin "2") (pinfunction "2_2") (pintype "passive"))
      (node (ref "R1") (pin "2") (pinfunction "2_2") (pintype "passive"))
      (node (ref "U1") (pin "3") (pinfunction "T-_3") (pintype "input"))
    )
    (net (code "75") (name "Net-(U2-Vcap)") (class "Default")
      (node (ref "C6") (pin "2") (pinfunction "2_2") (pintype "passive"))
      (node (ref "U2") (pin "56") (pinfunction "Vcap_56") (pintype "passive"))
    )
    (net (code "76") (name "Vpp") (class "Default")
      (node (ref "C10") (pin "1") (pinfunction "1_1") (pintype "passive"))
      (node (ref "C11") (pin "1") (pinfunction "1_1") (pintype "passive"))
      (node (ref "C18") (pin "2") (pinfunction "2_2") (pintype "passive"))
      (node (ref "C19") (pin "2") (pinfunction "2_2") (pintype "passive"))
      (node (ref "C3") (pin "2") (pinfunction "2_2") (pintype "passive"))
      (node (ref "C4") (pin "2") (pinfunction "2_2") (pintype "passive"))
      (node (ref "C7") (pin "1") (pinfunction "1_1") (pintype "passive"))
      (node (ref "C8") (pin "1") (pinfunction "1_1") (pintype "passive"))
      (node (ref "C9") (pin "1") (pinfunction "1_1") (pintype "passive"))
      (node (ref "J2") (pin "2") (pinfunction "2_2") (pintype "passive"))
      (node (ref "R11") (pin "1") (pinfunction "1_1") (pintype "passive"))
      (node (ref "R13") (pin "1") (pinfunction "1_1") (pintype "passive"))
      (node (ref "R14") (pin "1") (pinfunction "1_1") (pintype "passive"))
      (node (ref "R18") (pin "2") (pinfunction "2_2") (pintype "passive"))
      (node (ref "R45") (pin "1") (pinfunction "1_1") (pintype "passive"))
      (node (ref "U1") (pin "8") (pinfunction "DVDD_8") (pintype "power_in"))
      (node (ref "U2") (pin "10") (pinfunction "Vdd_10") (pintype "passive"))
      (node (ref "U2") (pin "19") (pinfunction "AVdd_19") (pintype "passive"))
      (node (ref "U2") (pin "26") (pinfunction "Vdd_26") (pintype "passive"))
      (node (ref "U2") (pin "35") (pinfunction "Vusb3v3_35") (pintype "passive"))
      (node (ref "U2") (pin "38") (pinfunction "Vdd_38") (pintype "passive"))
      (node (ref "U2") (pin "57") (pinfunction "Vdd_57") (pintype "passive"))
      (node (ref "U3") (pin "1") (pinfunction "VOUT_1") (pintype "power_in"))
    )
    (net (code "77") (name "unconnected-(J1-ID-Pad4)") (class "Default")
      (node (ref "J1") (pin "4") (pinfunction "ID_4") (pintype "passive"))
    )
    (net (code "78") (name "unconnected-(J2-Pad6)") (class "Default")
      (node (ref "J2") (pin "6") (pinfunction "6_6") (pintype "passive"))
    )
    (net (code "79") (name "unconnected-(SD1-CD{slash}DAT3-Pad1)") (class "Default")
      (node (ref "SD1") (pin "1") (pinfunction "CD/DAT3_1") (pintype "passive"))
    )
    (net (code "80") (name "unconnected-(SD1-DAT1-Pad8)") (class "Default")
      (node (ref "SD1") (pin "8") (pinfunction "DAT1_8") (pintype "passive"))
    )
    (net (code "81") (name "unconnected-(SD1-VDD-Pad4)") (class "Default")
      (node (ref "SD1") (pin "4") (pinfunction "VDD_4") (pintype "passive"))
    )
    (net (code "82") (name "unconnected-(SD1-VSS2-Pad6)") (class "Default")
      (node (ref "SD1") (pin "6") (pinfunction "VSS2_6") (pintype "passive"))
    )
    (net (code "83") (name "unconnected-(U1-NC-Pad6)") (class "Default")
      (node (ref "U1") (pin "6") (pinfunction "NC_6") (pintype "passive"))
    )
    (net (code "84") (name "unconnected-(U2-AN4{slash}C1INB{slash}RB4-Pad12)") (class "Default")
      (node (ref "U2") (pin "12") (pinfunction "AN4/C1INB/RB4_12") (pintype "passive"))
    )
    (net (code "85") (name "unconnected-(U2-AN5{slash}C1INA{slash}RPB5{slash}Vbuson{slash}RB5-Pad11)") (class "Default")
      (node (ref "U2") (pin "11") (pinfunction "AN5/C1INA/RPB5/Vbuson/RB5_11") (pintype "passive"))
    )
    (net (code "86") (name "unconnected-(U2-AN8{slash}RPB8{slash}CTED10{slash}RB8-Pad21)") (class "Default")
      (node (ref "U2") (pin "21") (pinfunction "AN8/RPB8/CTED10/RB8_21") (pintype "passive"))
    )
    (net (code "87") (name "unconnected-(U2-AN9{slash}RPB9{slash}CTED4{slash}PMA7{slash}RB9-Pad22)") (class "Default")
      (node (ref "U2") (pin "22") (pinfunction "AN9/RPB9/CTED4/PMA7/RB9_22") (pintype "passive"))
    )
    (net (code "88") (name "unconnected-(U2-AN22{slash}RPE5{slash}PMD5{slash}RE5-Pad1)") (class "Default")
      (node (ref "U2") (pin "1") (pinfunction "AN22/RPE5/PMD5/RE5_1") (pintype "passive"))
    )
    (net (code "89") (name "unconnected-(U2-AN27{slash}PMD7{slash}RE7-Pad3)") (class "Default")
      (node (ref "U2") (pin "3") (pinfunction "AN27/PMD7/RE7_3") (pintype "passive"))
    )
    (net (code "90") (name "unconnected-(U2-PGEC2{slash}AN6{slash}RPB6{slash}RB6-Pad17)") (class "Default")
      (node (ref "U2") (pin "17") (pinfunction "PGEC2/AN6/RPB6/RB6_17") (pintype "passive"))
    )
    (net (code "91") (name "unconnected-(U2-PGEC3{slash}AN2{slash}C2INB{slash}RPB2{slash}CTED13{slash}RB2-Pad14)") (class "Default")
      (node (ref "U2") (pin "14") (pinfunction "PGEC3/AN2/C2INB/RPB2/CTED13/RB2_14") (pintype "passive"))
    )
    (net (code "92") (name "unconnected-(U2-PGED2{slash}AN7{slash}RPB7{slash}CTED3{slash}RB7-Pad18)") (class "Default")
      (node (ref "U2") (pin "18") (pinfunction "PGED2/AN7/RPB7/CTED3/RB7_18") (pintype "passive"))
    )
    (net (code "93") (name "unconnected-(U2-PGED3{slash}AN3{slash}C2INA{slash}RPB3{slash}RB3-Pad13)") (class "Default")
      (node (ref "U2") (pin "13") (pinfunction "PGED3/AN3/C2INA/RPB3/RB3_13") (pintype "passive"))
    )
    (net (code "94") (name "unconnected-(U2-RD6-Pad54)") (class "Default")
      (node (ref "U2") (pin "54") (pinfunction "RD6_54") (pintype "passive"))
    )
    (net (code "95") (name "unconnected-(U2-TMS{slash}Cvrefout{slash}AN10{slash}RPB10{slash}CTED11{slash}PMA13{slash}RB10-Pad23)") (class "Default")
      (node (ref "U2") (pin "23") (pinfunction "TMS/Cvrefout/AN10/RPB10/CTED11/PMA13/RB10_23") (pintype "passive"))
    )
  )
)
